# Adafruit_Ultimate_GPS.net
KiCad netlist of a schematic drawn in EAGLE
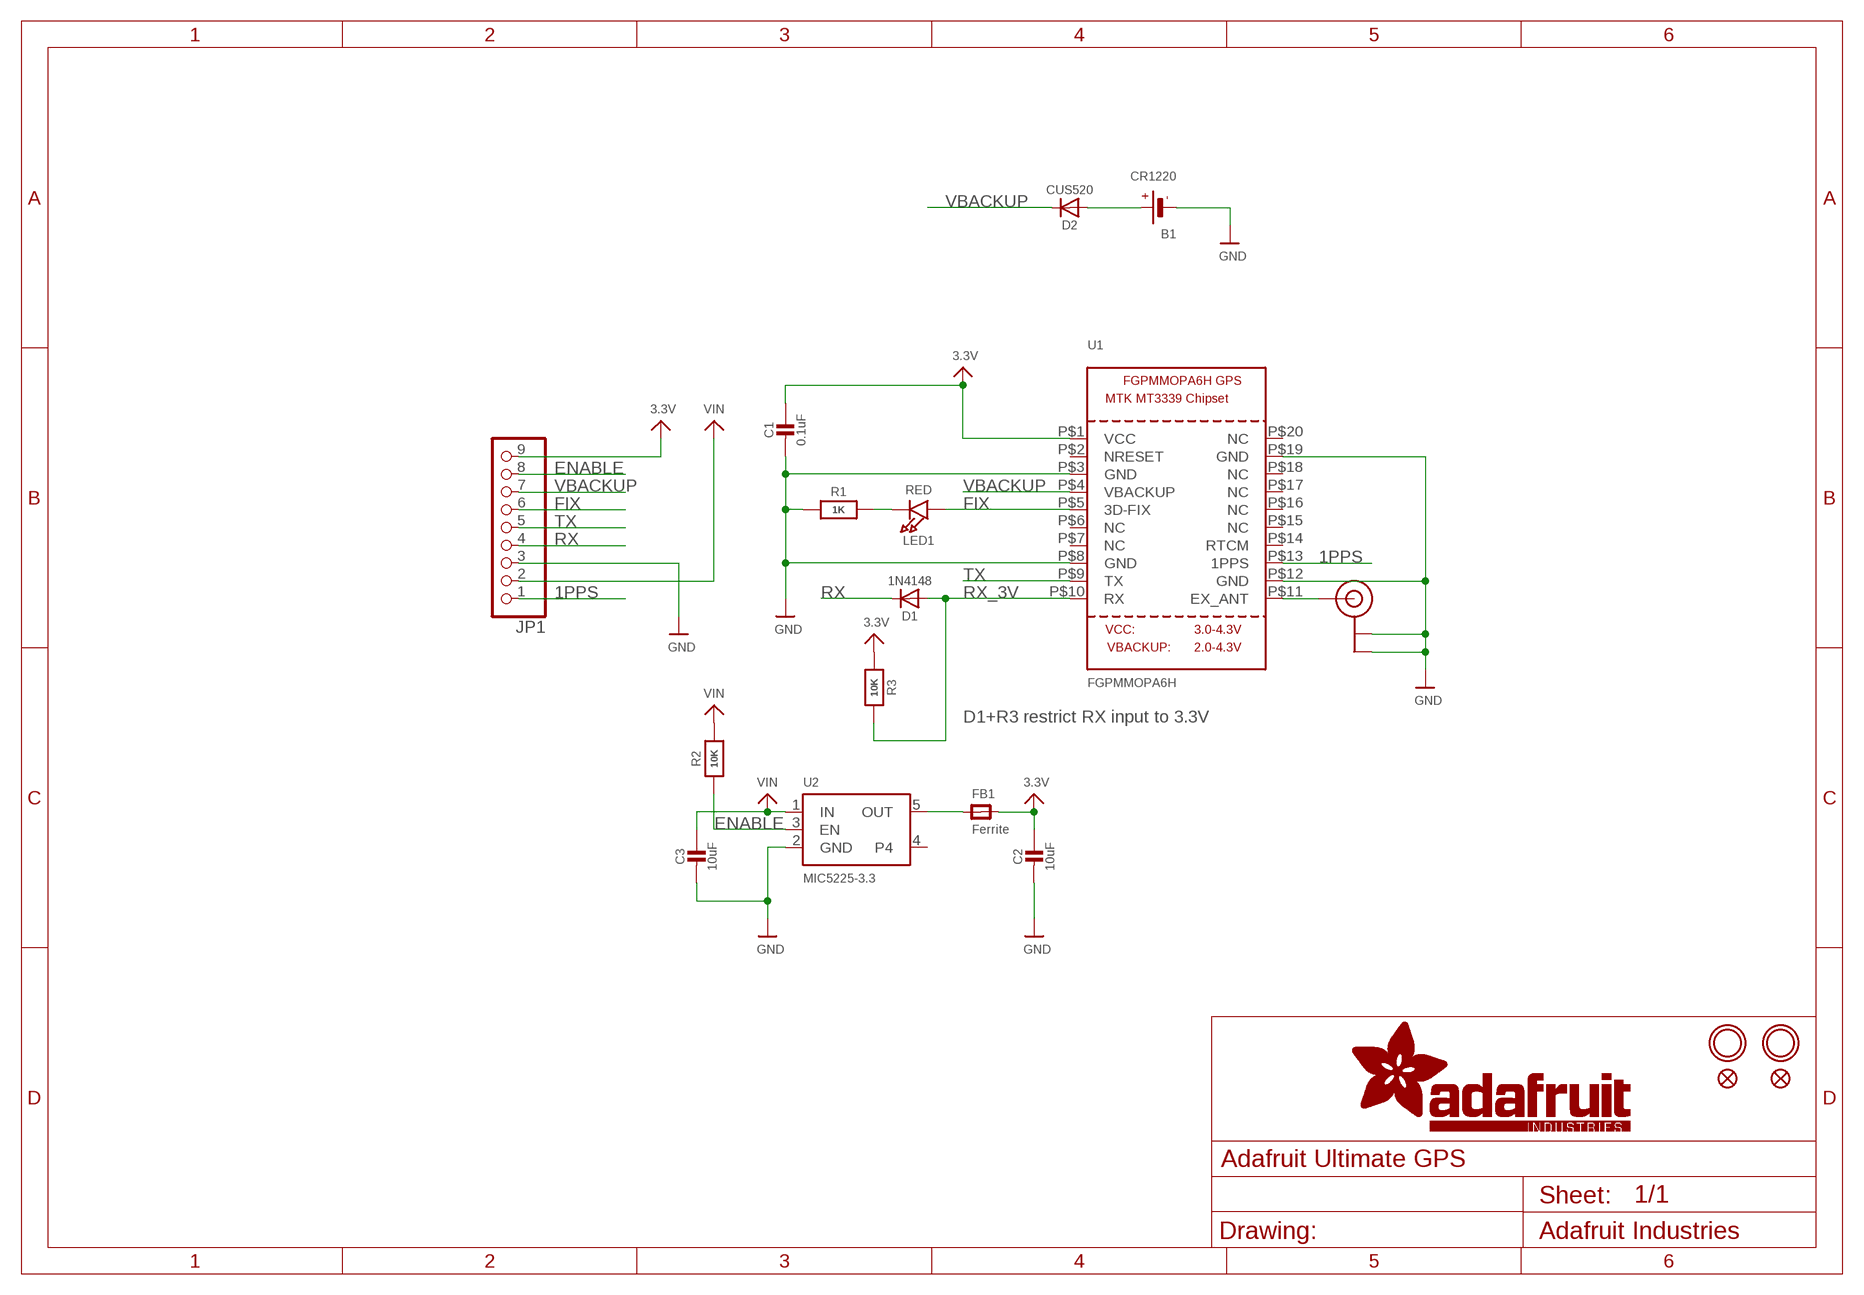
[diagram p0: schematic, sheet 1]

(export (version "E")
  (design (tool "Eeschema 10.0.6"))
  (components
    (comp (ref "B1")
      (value "CR1220")
      (footprint "eagle-import:CR1220")
      (libsource (lib "eagle-import") (part "BATTERYCR1220_SMT"))
    )
    (comp (ref "C1")
      (value "0.1uF")
      (footprint "eagle-import:0805-NO")
      (libsource (lib "eagle-import") (part "CAP_CERAMIC0805-NOOUTLINE"))
    )
    (comp (ref "C2")
      (value "10uF")
      (footprint "eagle-import:0805-NO")
      (libsource (lib "eagle-import") (part "CAP_CERAMIC0805-NOOUTLINE"))
    )
    (comp (ref "C3")
      (value "10uF")
      (footprint "eagle-import:0805-NO")
      (libsource (lib "eagle-import") (part "CAP_CERAMIC0805-NOOUTLINE"))
    )
    (comp (ref "D1")
      (value "1N4148")
      (footprint "eagle-import:SOD-323")
      (libsource (lib "eagle-import") (part "DIODESOD-323"))
    )
    (comp (ref "D2")
      (value "CUS520")
      (footprint "eagle-import:SOD-323")
      (libsource (lib "eagle-import") (part "DIODESOD-323"))
    )
    (comp (ref "FB1")
      (value "Ferrite")
      (footprint "eagle-import:0805-NO")
      (libsource (lib "eagle-import") (part "FERRITE-0805NO"))
    )
    (comp (ref "FID1")
      (value "FIDUCIAL\"\"")
      (footprint "eagle-import:FIDUCIAL_1MM")
      (libsource (lib "eagle-import") (part "FIDUCIAL{dblquote}{dblquote}"))
    )
    (comp (ref "FID2")
      (value "FIDUCIAL\"\"")
      (footprint "eagle-import:FIDUCIAL_1MM")
      (libsource (lib "eagle-import") (part "FIDUCIAL{dblquote}{dblquote}"))
    )
    (comp (ref "JP1")
      (value "HEADER-1X970MIL")
      (footprint "eagle-import:1X09_ROUND_70")
      (libsource (lib "eagle-import") (part "HEADER-1X970MIL"))
    )
    (comp (ref "LED1")
      (value "RED")
      (footprint "eagle-import:CHIPLED_0805")
      (libsource (lib "eagle-import") (part "LED0805"))
    )
    (comp (ref "R1")
      (value "1K")
      (footprint "eagle-import:0805-NO")
      (libsource (lib "eagle-import") (part "RESISTOR0805_NOOUTLINE"))
    )
    (comp (ref "R2")
      (value "10K")
      (footprint "eagle-import:0805-NO")
      (libsource (lib "eagle-import") (part "RESISTOR0805_NOOUTLINE"))
    )
    (comp (ref "R3")
      (value "10K")
      (footprint "eagle-import:0805-NO")
      (libsource (lib "eagle-import") (part "RESISTOR0805_NOOUTLINE"))
    )
    (comp (ref "U$8")
      (value "MOUNTINGHOLE2.5")
      (footprint "eagle-import:MOUNTINGHOLE_2.5_PLATED")
      (libsource (lib "eagle-import") (part "MOUNTINGHOLE2.5"))
    )
    (comp (ref "U$9")
      (value "MOUNTINGHOLE2.5")
      (footprint "eagle-import:MOUNTINGHOLE_2.5_PLATED")
      (libsource (lib "eagle-import") (part "MOUNTINGHOLE2.5"))
    )
    (comp (ref "U$20")
      (value "U.FL")
      (footprint "eagle-import:U.FL")
      (libsource (lib "eagle-import") (part "U.FL"))
    )
    (comp (ref "U1")
      (value "FGPMMOPA6H")
      (footprint "eagle-import:FGPMMOPA6H")
      (libsource (lib "eagle-import") (part "GPS_FGPMMOPA6H"))
    )
    (comp (ref "U2")
      (value "MIC5225-3.3")
      (footprint "eagle-import:SOT23-5")
      (libsource (lib "eagle-import") (part "VREG_SOT23-5"))
    )
  )
  (nets
    (net (code "1") (name "/1PPS") (class "Default")
      (node (ref "JP1") (pin "1") (pinfunction "1_1") (pintype "passive"))
      (node (ref "U1") (pin "P$13") (pinfunction "1PPS_P$13") (pintype "bidirectional"))
    )
    (net (code "2") (name "/ENABLE") (class "Default")
      (node (ref "JP1") (pin "8") (pinfunction "8_8") (pintype "passive"))
      (node (ref "R2") (pin "1") (pinfunction "1_1") (pintype "passive"))
      (node (ref "U2") (pin "3") (pinfunction "EN_3") (pintype "input"))
    )
    (net (code "3") (name "/FIX") (class "Default")
      (node (ref "JP1") (pin "6") (pinfunction "6_6") (pintype "passive"))
      (node (ref "LED1") (pin "A") (pinfunction "A_A") (pintype "passive"))
      (node (ref "U1") (pin "P$5") (pinfunction "3D-FIX_P$5") (pintype "bidirectional"))
    )
    (net (code "4") (name "/RX") (class "Default")
      (node (ref "D1") (pin "C") (pinfunction "C_C") (pintype "passive"))
      (node (ref "JP1") (pin "4") (pinfunction "4_4") (pintype "passive"))
    )
    (net (code "5") (name "/RX_3V") (class "Default")
      (node (ref "D1") (pin "A") (pinfunction "A_A") (pintype "passive"))
      (node (ref "R3") (pin "2") (pinfunction "2_2") (pintype "passive"))
      (node (ref "U1") (pin "P$10") (pinfunction "RX_P$10") (pintype "bidirectional"))
    )
    (net (code "6") (name "/TX") (class "Default")
      (node (ref "JP1") (pin "5") (pinfunction "5_5") (pintype "passive"))
      (node (ref "U1") (pin "P$9") (pinfunction "TX_P$9") (pintype "bidirectional"))
    )
    (net (code "7") (name "/VBACKUP") (class "Default")
      (node (ref "D2") (pin "C") (pinfunction "C_C") (pintype "passive"))
      (node (ref "JP1") (pin "7") (pinfunction "7_7") (pintype "passive"))
      (node (ref "U1") (pin "P$4") (pinfunction "VBACKUP_P$4") (pintype "bidirectional"))
    )
    (net (code "8") (name "3.3V") (class "Default")
      (node (ref "C1") (pin "1") (pinfunction "1_1") (pintype "passive"))
      (node (ref "C2") (pin "1") (pinfunction "1_1") (pintype "passive"))
      (node (ref "FB1") (pin "2") (pinfunction "P$2_2") (pintype "passive"))
      (node (ref "JP1") (pin "9") (pinfunction "9_9") (pintype "passive"))
      (node (ref "R3") (pin "1") (pinfunction "1_1") (pintype "passive"))
      (node (ref "U1") (pin "P$1") (pinfunction "VCC_P$1") (pintype "bidirectional"))
    )
    (net (code "9") (name "GND") (class "Default")
      (node (ref "B1") (pin "-") (pinfunction "-_-") (pintype "passive"))
      (node (ref "C1") (pin "2") (pinfunction "2_2") (pintype "passive"))
      (node (ref "C2") (pin "2") (pinfunction "2_2") (pintype "passive"))
      (node (ref "C3") (pin "2") (pinfunction "2_2") (pintype "passive"))
      (node (ref "JP1") (pin "3") (pinfunction "3_3") (pintype "passive"))
      (node (ref "R1") (pin "1") (pinfunction "1_1") (pintype "passive"))
      (node (ref "U$20") (pin "P$1") (pinfunction "GND_P$1") (pintype "bidirectional"))
      (node (ref "U$20") (pin "P$2") (pinfunction "GND_P$2") (pintype "bidirectional"))
      (node (ref "U1") (pin "P$12") (pinfunction "GND_P$12") (pintype "bidirectional"))
      (node (ref "U1") (pin "P$19") (pinfunction "GND_P$19") (pintype "bidirectional"))
      (node (ref "U1") (pin "P$3") (pinfunction "GND_P$3") (pintype "bidirectional"))
      (node (ref "U1") (pin "P$8") (pinfunction "GND_P$8") (pintype "bidirectional"))
      (node (ref "U2") (pin "2") (pinfunction "GND_2") (pintype "power_in"))
    )
    (net (code "10") (name "Net-(B1-+-Pad+$1)") (class "Default")
      (node (ref "B1") (pin "+$1") (pinfunction "+_+$1") (pintype "passive"))
      (node (ref "B1") (pin "+$2") (pinfunction "+_+$2") (pintype "passive"))
      (node (ref "D2") (pin "A") (pinfunction "A_A") (pintype "passive"))
    )
    (net (code "11") (name "Net-(FB1-P$1)") (class "Default")
      (node (ref "FB1") (pin "1") (pinfunction "P$1_1") (pintype "passive"))
      (node (ref "U2") (pin "5") (pinfunction "OUT_5") (pintype "power_in"))
    )
    (net (code "12") (name "Net-(LED1-PadC)") (class "Default")
      (node (ref "LED1") (pin "C") (pinfunction "C_C") (pintype "passive"))
      (node (ref "R1") (pin "2") (pinfunction "2_2") (pintype "passive"))
    )
    (net (code "13") (name "Net-(U$20-SIGNAL)") (class "Default")
      (node (ref "U$20") (pin "P$3") (pinfunction "SIGNAL_P$3") (pintype "bidirectional"))
      (node (ref "U1") (pin "P$11") (pinfunction "EX_ANT_P$11") (pintype "bidirectional"))
    )
    (net (code "14") (name "VIN") (class "Default")
      (node (ref "C3") (pin "1") (pinfunction "1_1") (pintype "passive"))
      (node (ref "JP1") (pin "2") (pinfunction "2_2") (pintype "passive"))
      (node (ref "R2") (pin "2") (pinfunction "2_2") (pintype "passive"))
      (node (ref "U2") (pin "1") (pinfunction "IN_1") (pintype "power_in"))
    )
    (net (code "15") (name "unconnected-(U1-NC-PadP$6)") (class "Default")
      (node (ref "U1") (pin "P$6") (pinfunction "NC_P$6") (pintype "bidirectional"))
    )
    (net (code "16") (name "unconnected-(U1-NC-PadP$7)") (class "Default")
      (node (ref "U1") (pin "P$7") (pinfunction "NC_P$7") (pintype "bidirectional"))
    )
    (net (code "17") (name "unconnected-(U1-NC-PadP$15)") (class "Default")
      (node (ref "U1") (pin "P$15") (pinfunction "NC_P$15") (pintype "bidirectional"))
    )
    (net (code "18") (name "unconnected-(U1-NC-PadP$16)") (class "Default")
      (node (ref "U1") (pin "P$16") (pinfunction "NC_P$16") (pintype "bidirectional"))
    )
    (net (code "19") (name "unconnected-(U1-NC-PadP$17)") (class "Default")
      (node (ref "U1") (pin "P$17") (pinfunction "NC_P$17") (pintype "bidirectional"))
    )
    (net (code "20") (name "unconnected-(U1-NC-PadP$18)") (class "Default")
      (node (ref "U1") (pin "P$18") (pinfunction "NC_P$18") (pintype "bidirectional"))
    )
    (net (code "21") (name "unconnected-(U1-NC-PadP$20)") (class "Default")
      (node (ref "U1") (pin "P$20") (pinfunction "NC_P$20") (pintype "bidirectional"))
    )
    (net (code "22") (name "unconnected-(U1-NRESET-PadP$2)") (class "Default")
      (node (ref "U1") (pin "P$2") (pinfunction "NRESET_P$2") (pintype "bidirectional"))
    )
    (net (code "23") (name "unconnected-(U1-RTCM-PadP$14)") (class "Default")
      (node (ref "U1") (pin "P$14") (pinfunction "RTCM_P$14") (pintype "bidirectional"))
    )
    (net (code "24") (name "unconnected-(U2-P4-Pad4)") (class "Default")
      (node (ref "U2") (pin "4") (pinfunction "P4_4") (pintype "bidirectional"))
    )
  )
)
